# MCU.net
KiCad netlist of a schematic drawn in Altium Designer
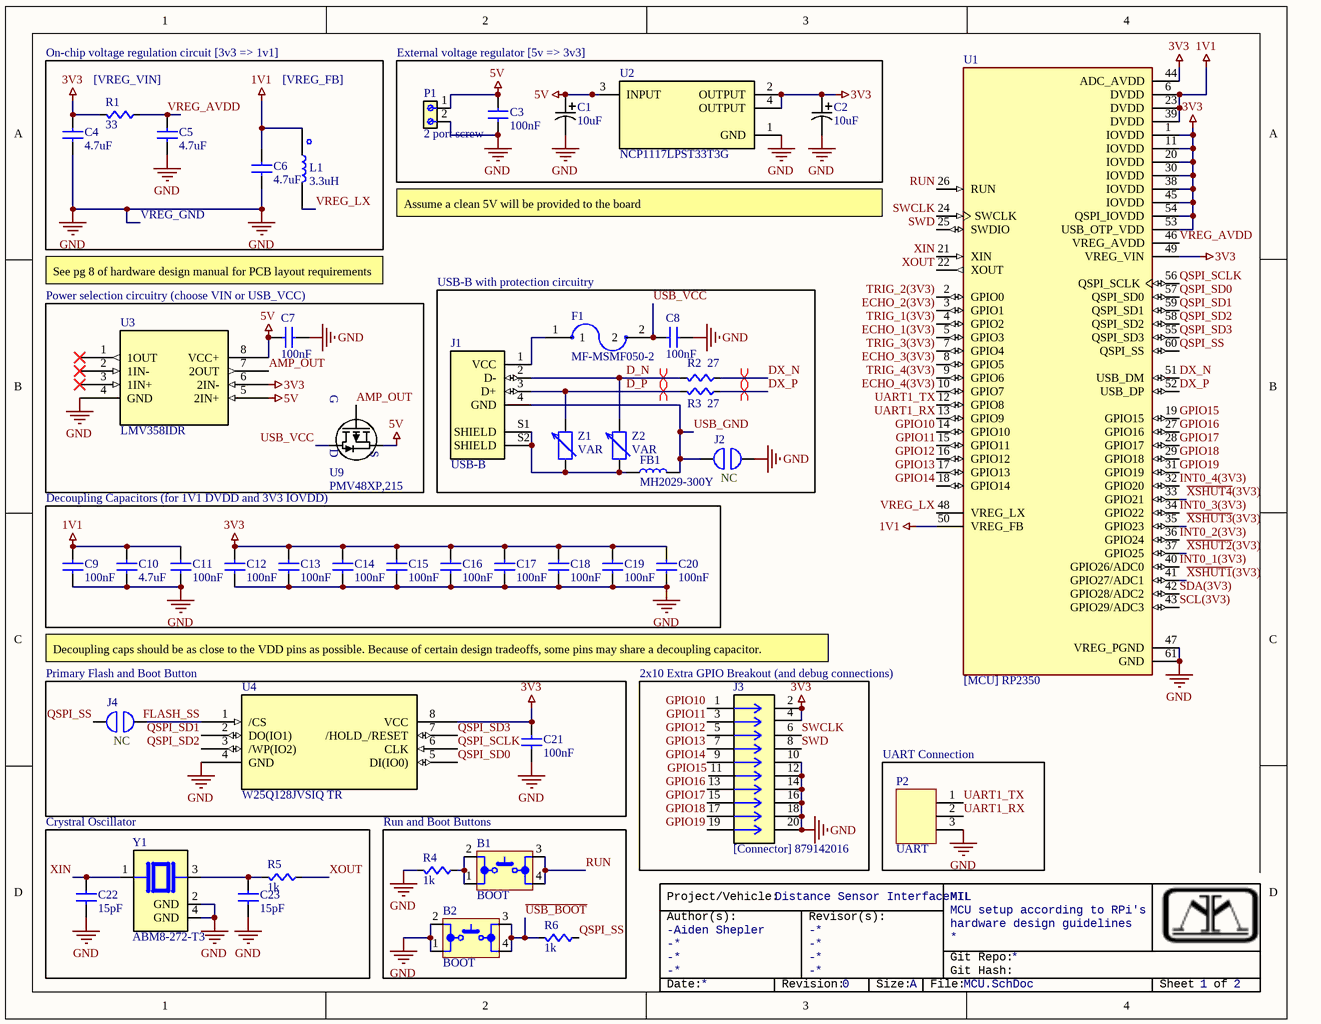
[diagram p0: MCU.SchDoc]

(export (version "E")
  (design (tool "Eeschema 10.0.6"))
  (components
    (comp (ref "B1")
      (value "BOOT")
      (footprint "SPST-PUSH-BUTTON")
      (description "SWITCH TACTILE SPST-NO 0.05A 24V")
      (fields
        (field (name "MANUFACTURER") "TE Connectivity Alcoswitch")
        (field (name "MANUFACTURER PART NUMBER") "1825910-6")
      )
      (libsource (lib "Alexandria") (part "1825910-6"))
    )
    (comp (ref "B2")
      (value "BOOT")
      (footprint "SPST-PUSH-BUTTON")
      (description "SWITCH TACTILE SPST-NO 0.05A 24V")
      (fields
        (field (name "MANUFACTURER") "TE Connectivity Alcoswitch")
        (field (name "MANUFACTURER PART NUMBER") "1825910-6")
      )
      (libsource (lib "Alexandria") (part "1825910-6"))
    )
    (comp (ref "C1")
      (value "10uF")
      (footprint "RADIAL_CAN_CAP_4_X_5.8_SMD")
      (description "10uF electrolytic cap, radial can, SMD")
      (fields
        (field (name "MANUFACTURER_PART_NUMBER") "EEE-FK1E100R")
        (field (name "COPYRIGHT") "Copyright (C) 2025 Ultra Librarian. All rights reserved.")
      )
      (libsource (lib "Alexandria") (part "EEE-FK1E100R"))
    )
    (comp (ref "C2")
      (value "10uF")
      (footprint "RADIAL_CAN_CAP_4_X_5.8_SMD")
      (description "10uF electrolytic cap, radial can, SMD")
      (fields
        (field (name "MANUFACTURER_PART_NUMBER") "EEE-FK1E100R")
        (field (name "COPYRIGHT") "Copyright (C) 2025 Ultra Librarian. All rights reserved.")
      )
      (libsource (lib "Alexandria") (part "EEE-FK1E100R"))
    )
    (comp (ref "C3")
      (value "100nF")
      (footprint "CAPC0603")
      (fields (field (name "Comment") "Cap"))
      (libsource (lib "Passives") (part "Cap"))
    )
    (comp (ref "C4")
      (value "4.7uF")
      (footprint "CAPC0603")
      (fields (field (name "Comment") "Cap"))
      (libsource (lib "Passives") (part "Cap"))
    )
    (comp (ref "C5")
      (value "4.7uF")
      (footprint "CAPC0603")
      (fields (field (name "Comment") "Cap"))
      (libsource (lib "Passives") (part "Cap"))
    )
    (comp (ref "C6")
      (value "4.7uF")
      (footprint "CAPC0603")
      (fields (field (name "Comment") "Cap"))
      (libsource (lib "Passives") (part "Cap"))
    )
    (comp (ref "C7")
      (value "100nF")
      (footprint "CAPC0603")
      (fields (field (name "Comment") "Cap"))
      (libsource (lib "Passives") (part "Cap"))
    )
    (comp (ref "C8")
      (value "100nF")
      (footprint "CAPC0603")
      (fields (field (name "Comment") "Cap"))
      (libsource (lib "Passives") (part "Cap"))
    )
    (comp (ref "C9")
      (value "100nF")
      (footprint "CAPC0603")
      (fields (field (name "Comment") "Cap"))
      (libsource (lib "Passives") (part "Cap"))
    )
    (comp (ref "C10")
      (value "4.7uF")
      (footprint "CAPC0603")
      (fields (field (name "Comment") "Cap"))
      (libsource (lib "Passives") (part "Cap"))
    )
    (comp (ref "C11")
      (value "100nF")
      (footprint "CAPC0603")
      (fields (field (name "Comment") "Cap"))
      (libsource (lib "Passives") (part "Cap"))
    )
    (comp (ref "C12")
      (value "100nF")
      (footprint "CAPC0603")
      (fields (field (name "Comment") "Cap"))
      (libsource (lib "Passives") (part "Cap"))
    )
    (comp (ref "C13")
      (value "100nF")
      (footprint "CAPC0603")
      (fields (field (name "Comment") "Cap"))
      (libsource (lib "Passives") (part "Cap"))
    )
    (comp (ref "C14")
      (value "100nF")
      (footprint "CAPC0603")
      (fields (field (name "Comment") "Cap"))
      (libsource (lib "Passives") (part "Cap"))
    )
    (comp (ref "C15")
      (value "100nF")
      (footprint "CAPC0603")
      (fields (field (name "Comment") "Cap"))
      (libsource (lib "Passives") (part "Cap"))
    )
    (comp (ref "C16")
      (value "100nF")
      (footprint "CAPC0603")
      (fields (field (name "Comment") "Cap"))
      (libsource (lib "Passives") (part "Cap"))
    )
    (comp (ref "C17")
      (value "100nF")
      (footprint "CAPC0603")
      (fields (field (name "Comment") "Cap"))
      (libsource (lib "Passives") (part "Cap"))
    )
    (comp (ref "C18")
      (value "100nF")
      (footprint "CAPC0603")
      (fields (field (name "Comment") "Cap"))
      (libsource (lib "Passives") (part "Cap"))
    )
    (comp (ref "C19")
      (value "100nF")
      (footprint "CAPC0603")
      (fields (field (name "Comment") "Cap"))
      (libsource (lib "Passives") (part "Cap"))
    )
    (comp (ref "C20")
      (value "100nF")
      (footprint "CAPC0603")
      (fields (field (name "Comment") "Cap"))
      (libsource (lib "Passives") (part "Cap"))
    )
    (comp (ref "C21")
      (value "100nF")
      (footprint "CAPC0603")
      (fields (field (name "Comment") "Cap"))
      (libsource (lib "Passives") (part "Cap"))
    )
    (comp (ref "C22")
      (value "15pF")
      (footprint "CAPC0603")
      (fields (field (name "Comment") "Cap"))
      (libsource (lib "Passives") (part "Cap"))
    )
    (comp (ref "C23")
      (value "15pF")
      (footprint "CAPC0603")
      (fields (field (name "Comment") "Cap"))
      (libsource (lib "Passives") (part "Cap"))
    )
    (comp (ref "F1")
      (value "MF-MSMF050-2")
      (footprint "FUSM4632X85")
      (description "[Fuse] Polymeric PTC Resettable Fuse 15V 500 mA Ih Surface Mount 1812 (4532 Metric), Concave")
      (fields (field (name "MF") "Bourns"))
      (libsource (lib "Alexandria") (part "MF-MSMF050-2"))
    )
    (comp (ref "FB1")
      (value "MH2029-300Y")
      (footprint "L0805")
      (description "[Inductor] Ferrite Bead Bourns MH2029-300Y\r\nSMD-FERRITE-BEAD-30R-3A(0805)")
      (fields (field (name "MF") "Bourns"))
      (libsource (lib "Alexandria") (part "MH2029-300Y"))
    )
    (comp (ref "J1")
      (value "USB-B")
      (footprint "SAMTEC_USB-B-S-X-X-TH")
      (description "USB-B (USB TYPE-B) USB 2.0 Receptacle Connector 4 Position Through Hole, Right Angle")
      (fields (field (name "MF") "Samtec") (field (name "MP") "USB-B-S-F-W-TH-TR"))
      (libsource (lib "Alexandria") (part "USB-B-S-X-X-TH"))
    )
    (comp (ref "J2")
      (value "Thru-Hole Jumper")
      (footprint "[Jumper] Solderable Jumper")
      (description "Clip Jumper")
      (fields (field (name "NO/NC") "NC"))
      (libsource (lib "Alexandria") (part "[Jump] Thru-Hole 2pin"))
    )
    (comp (ref "J3")
      (value "[Connector] 879142016")
      (footprint "[Connector] CONN20")
      (description "2x10 2.54mm pitch header")
      (fields (field (name "MP") "879142016"))
      (libsource (lib "Alexandria") (part "[Connector] 879142016"))
    )
    (comp (ref "J4")
      (value "Thru-Hole Jumper")
      (footprint "[Jumper] Solderable Jumper")
      (description "Clip Jumper")
      (fields (field (name "NO/NC") "NC"))
      (libsource (lib "Alexandria") (part "[Jump] Thru-Hole 2pin"))
    )
    (comp (ref "L1")
      (value "3.3uH")
      (footprint "2016_SMD_Inductor")
      (description "Power Inductors - SMD IND 3.3uH used for RP2350 VREG")
      (fields
        (field (name "MOUSER PART NUMBER") "815-AB201610S3R3101T")
        (field (name "MANUFACTURER_PART_NUMBER") "AOTA-B201610S3R3-101-T")
      )
      (libsource (lib "Alexandria") (part "INDUCTOR 3.3uH"))
    )
    (comp (ref "P1")
      (value "2 port screw")
      (footprint "[CONNECTOR] 5MM_2PORT_SCREW")
      (description "2 Position Wire to Board Terminal Block Horizontal with Board 0.200 (5.08mm) Through Hole")
      (fields (field (name "MF") "WÃ¼rth Elektronik") (field (name "MP") "691213510002"))
      (libsource (lib "Alexandria") (part "[Connector] 691213510002"))
    )
    (comp (ref "P2")
      (value "UART")
      (footprint "MOLEX-HDR-1X3-SHERLOCK-RA")
      (description "Header, Molex, 2mm Pitch Sherlock Header, Single Row, Right Angle 3 Circuits, Length 3.3mm")
      (fields
        (field (name "MANUFACTURER PART NUMBER") "35363-0360")
        (field (name "MANUFACTURER") "Molex Connector Corporation")
      )
      (libsource (lib "Connectors") (part "MOLEX-HDR-1x3-SHERLOCK_RA"))
    )
    (comp (ref "R1")
      (value "33")
      (footprint "RES0603")
      (description "SMD, RES0603")
      (fields (field (name "Comment") "Res"))
      (libsource (lib "Passives") (part "Res"))
    )
    (comp (ref "R2")
      (value "27")
      (footprint "RES0603")
      (description "SMD, RES0603")
      (fields (field (name "Comment") "Res"))
      (libsource (lib "Passives") (part "Res"))
    )
    (comp (ref "R3")
      (value "27")
      (footprint "RES0603")
      (description "SMD, RES0603")
      (fields (field (name "Comment") "Res"))
      (libsource (lib "Passives") (part "Res"))
    )
    (comp (ref "R4")
      (value "1k")
      (footprint "RES0603")
      (description "SMD, RES0603")
      (fields (field (name "Comment") "Res"))
      (libsource (lib "Passives") (part "Res"))
    )
    (comp (ref "R5")
      (value "1k")
      (footprint "RES0603")
      (description "SMD, RES0603")
      (fields (field (name "Comment") "Res"))
      (libsource (lib "Passives") (part "Res"))
    )
    (comp (ref "R6")
      (value "1k")
      (footprint "RES0603")
      (description "SMD, RES0603")
      (fields (field (name "Comment") "Res"))
      (libsource (lib "Passives") (part "Res"))
    )
    (comp (ref "U1")
      (value "[MCU] RP2350")
      (footprint "QFN40P700X700X90-61N")
      (description "RP2350A MCU from Raspberry Pi Pico; QFN 60 7x7,")
      (fields (field (name "MF") "Raspberry Pi") (field (name "MP") "SC1509-A4"))
      (libsource (lib "Alexandria") (part "SC1509(13)"))
    )
    (comp (ref "U2")
      (value "NCP1117LPST33T3G")
      (footprint "SOT230P700X175-4N")
      (description "Linear Voltage Regulator IC Positive Fixed 1 Output 1A SOT-223")
      (fields (field (name "MF") "ON Semiconductor"))
      (libsource (lib "Alexandria") (part "NCP1117LPST33T3G"))
    )
    (comp (ref "U3")
      (value "LMV358IDR")
      (footprint "SOIC-8")
      (description "[Op-Amp] Dual, 5.5-V, 1-MHz, RRO operational amplifier 8-SOIC -40 to 125")
      (fields (field (name "COPYRIGHT") "Copyright (C) 2025 Ultra Librarian. All rights reserved."))
      (libsource (lib "Alexandria") (part "LMV358IDR"))
    )
    (comp (ref "U4")
      (value "W25Q128JVSIQ TR")
      (footprint "SOIC_208MIL_WIN")
      (description "IC FLASH 128MBIT SPI/QUAD 8SOIC")
      (fields (field (name "COPYRIGHT") "Copyright (C) 2025 Ultra Librarian. All rights reserved."))
      (libsource (lib "Alexandria") (part "W25Q128JVSIQ TR"))
    )
    (comp (ref "U9")
      (value "PMV48XP,215")
      (footprint "SOT23_NEX")
      (description "MOSFET P-CH 20V 3.5A TO236AB")
      (fields (field (name "COPYRIGHT") "Copyright (C) 2025 Ultra Librarian. All rights reserved."))
      (libsource (lib "Alexandria") (part "[PMOS] PMV48XP,215"))
    )
    (comp (ref "Y1")
      (value "ABM8-272-T3")
      (footprint "XTAL_ABM8-272-T3")
      (description "12 MHz Â±30ppm Crystal 10pF 50 Ohms 4-SMD, No Lead")
      (fields (field (name "MF") "ABRACON"))
      (libsource (lib "Alexandria") (part "ABM8-272-T3"))
    )
    (comp (ref "Z1")
      (value "VAR")
      (footprint "VARC1608X56N")
      (description "[Varistor] 1 Circuit Surface Mount, MLCV 0603 (1608 Metric)")
      (fields (field (name "MP") "CG0603MLC-05E") (field (name "MF") "Bourns"))
      (libsource (lib "Alexandria") (part "CG0603MLC-05E"))
    )
    (comp (ref "Z2")
      (value "VAR")
      (footprint "VARC1608X56N")
      (description "[Varistor] 1 Circuit Surface Mount, MLCV 0603 (1608 Metric)")
      (fields (field (name "MP") "CG0603MLC-05E") (field (name "MF") "Bourns"))
      (libsource (lib "Alexandria") (part "CG0603MLC-05E"))
    )
  )
  (nets
    (net (code "1") (name "/AMP_OUT") (class "Default")
      (node (ref "U3") (pin "7") (pinfunction "2OUT_7") (pintype "output"))
      (node (ref "U9") (pin "1") (pinfunction "G_1") (pintype "passive"))
    )
    (net (code "2") (name "/DX_N") (class "Default")
      (node (ref "R2") (pin "2") (pinfunction "B_2") (pintype "passive"))
      (node (ref "U1") (pin "51") (pinfunction "USB_DM_51") (pintype "bidirectional"))
    )
    (net (code "3") (name "/DX_P") (class "Default")
      (node (ref "R3") (pin "2") (pinfunction "B_2") (pintype "passive"))
      (node (ref "U1") (pin "52") (pinfunction "USB_DP_52") (pintype "bidirectional"))
    )
    (net (code "4") (name "/D_N") (class "Default")
      (node (ref "J1") (pin "2") (pinfunction "D-_2") (pintype "bidirectional"))
      (node (ref "R2") (pin "1") (pinfunction "A_1") (pintype "passive"))
      (node (ref "Z2") (pin "2") (pinfunction "2_2") (pintype "passive"))
    )
    (net (code "5") (name "/D_P") (class "Default")
      (node (ref "J1") (pin "3") (pinfunction "D+_3") (pintype "bidirectional"))
      (node (ref "R3") (pin "1") (pinfunction "A_1") (pintype "passive"))
      (node (ref "Z1") (pin "2") (pinfunction "2_2") (pintype "passive"))
    )
    (net (code "6") (name "/ECHO_1(3V3)") (class "Default")
      (node (ref "U1") (pin "5") (pinfunction "GPIO3_5") (pintype "bidirectional"))
    )
    (net (code "7") (name "/ECHO_2(3V3)") (class "Default")
      (node (ref "U1") (pin "3") (pinfunction "GPIO1_3") (pintype "bidirectional"))
    )
    (net (code "8") (name "/ECHO_3(3V3)") (class "Default")
      (node (ref "U1") (pin "8") (pinfunction "GPIO5_8") (pintype "bidirectional"))
    )
    (net (code "9") (name "/ECHO_4(3V3)") (class "Default")
      (node (ref "U1") (pin "10") (pinfunction "GPIO7_10") (pintype "bidirectional"))
    )
    (net (code "10") (name "/FLASH_SS") (class "Default")
      (node (ref "J4") (pin "2") (pintype "passive"))
      (node (ref "U4") (pin "1") (pinfunction "/CS_1") (pintype "input"))
    )
    (net (code "11") (name "/GPIO10") (class "Default")
      (node (ref "J3") (pin "1") (pinfunction "1_1") (pintype "passive"))
      (node (ref "U1") (pin "14") (pinfunction "GPIO10_14") (pintype "bidirectional"))
    )
    (net (code "12") (name "/GPIO11") (class "Default")
      (node (ref "J3") (pin "3") (pinfunction "3_3") (pintype "passive"))
      (node (ref "U1") (pin "15") (pinfunction "GPIO11_15") (pintype "bidirectional"))
    )
    (net (code "13") (name "/GPIO12") (class "Default")
      (node (ref "J3") (pin "5") (pinfunction "5_5") (pintype "passive"))
      (node (ref "U1") (pin "16") (pinfunction "GPIO12_16") (pintype "bidirectional"))
    )
    (net (code "14") (name "/GPIO13") (class "Default")
      (node (ref "J3") (pin "7") (pinfunction "7_7") (pintype "passive"))
      (node (ref "U1") (pin "17") (pinfunction "GPIO13_17") (pintype "bidirectional"))
    )
    (net (code "15") (name "/GPIO14") (class "Default")
      (node (ref "J3") (pin "9") (pinfunction "9_9") (pintype "passive"))
      (node (ref "U1") (pin "18") (pinfunction "GPIO14_18") (pintype "bidirectional"))
    )
    (net (code "16") (name "/GPIO15") (class "Default")
      (node (ref "J3") (pin "11") (pinfunction "11_11") (pintype "passive"))
      (node (ref "U1") (pin "19") (pinfunction "GPIO15_19") (pintype "bidirectional"))
    )
    (net (code "17") (name "/GPIO16") (class "Default")
      (node (ref "J3") (pin "13") (pinfunction "13_13") (pintype "passive"))
      (node (ref "U1") (pin "27") (pinfunction "GPIO16_27") (pintype "bidirectional"))
    )
    (net (code "18") (name "/GPIO17") (class "Default")
      (node (ref "J3") (pin "15") (pinfunction "15_15") (pintype "passive"))
      (node (ref "U1") (pin "28") (pinfunction "GPIO17_28") (pintype "bidirectional"))
    )
    (net (code "19") (name "/GPIO18") (class "Default")
      (node (ref "J3") (pin "17") (pinfunction "17_17") (pintype "passive"))
      (node (ref "U1") (pin "29") (pinfunction "GPIO18_29") (pintype "bidirectional"))
    )
    (net (code "20") (name "/GPIO19") (class "Default")
      (node (ref "J3") (pin "19") (pinfunction "19_19") (pintype "passive"))
      (node (ref "U1") (pin "31") (pinfunction "GPIO19_31") (pintype "bidirectional"))
    )
    (net (code "21") (name "/INT0_1(3V3)") (class "Default")
      (node (ref "U1") (pin "40") (pinfunction "GPIO26/ADC0_40") (pintype "bidirectional"))
    )
    (net (code "22") (name "/INT0_2(3V3)") (class "Default")
      (node (ref "U1") (pin "36") (pinfunction "GPIO24_36") (pintype "bidirectional"))
    )
    (net (code "23") (name "/INT0_3(3V3)") (class "Default")
      (node (ref "U1") (pin "34") (pinfunction "GPIO22_34") (pintype "bidirectional"))
    )
    (net (code "24") (name "/INT0_4(3V3)") (class "Default")
      (node (ref "U1") (pin "32") (pinfunction "GPIO20_32") (pintype "bidirectional"))
    )
    (net (code "25") (name "/QSPI_SCLK") (class "Default")
      (node (ref "U1") (pin "56") (pinfunction "QSPI_SCLK_56") (pintype "bidirectional"))
      (node (ref "U4") (pin "6") (pinfunction "CLK_6") (pintype "input"))
    )
    (net (code "26") (name "/QSPI_SD0") (class "Default")
      (node (ref "U1") (pin "57") (pinfunction "QSPI_SD0_57") (pintype "bidirectional"))
      (node (ref "U4") (pin "5") (pinfunction "DI(IO0)_5") (pintype "bidirectional"))
    )
    (net (code "27") (name "/QSPI_SD1") (class "Default")
      (node (ref "U1") (pin "59") (pinfunction "QSPI_SD1_59") (pintype "bidirectional"))
      (node (ref "U4") (pin "2") (pinfunction "DO(IO1)_2") (pintype "bidirectional"))
    )
    (net (code "28") (name "/QSPI_SD2") (class "Default")
      (node (ref "U1") (pin "58") (pinfunction "QSPI_SD2_58") (pintype "bidirectional"))
      (node (ref "U4") (pin "3") (pinfunction "/WP(IO2)_3") (pintype "bidirectional"))
    )
    (net (code "29") (name "/QSPI_SD3") (class "Default")
      (node (ref "U1") (pin "55") (pinfunction "QSPI_SD3_55") (pintype "bidirectional"))
      (node (ref "U4") (pin "7") (pinfunction "/HOLD_/RESET_7") (pintype "bidirectional"))
    )
    (net (code "30") (name "/QSPI_SS") (class "Default")
      (node (ref "J4") (pin "1") (pintype "passive"))
      (node (ref "R6") (pin "2") (pinfunction "B_2") (pintype "passive"))
      (node (ref "U1") (pin "60") (pinfunction "QSPI_SS_60") (pintype "bidirectional"))
    )
    (net (code "31") (name "/RUN") (class "Default")
      (node (ref "B1") (pin "3") (pinfunction "3_3") (pintype "passive"))
      (node (ref "B1") (pin "4") (pinfunction "4_4") (pintype "passive"))
      (node (ref "U1") (pin "26") (pinfunction "RUN_26") (pintype "input"))
    )
    (net (code "32") (name "/SCL(3V3)") (class "Default")
      (node (ref "U1") (pin "43") (pinfunction "GPIO29/ADC3_43") (pintype "bidirectional"))
    )
    (net (code "33") (name "/SDA(3V3)") (class "Default")
      (node (ref "U1") (pin "42") (pinfunction "GPIO28/ADC2_42") (pintype "bidirectional"))
    )
    (net (code "34") (name "/SWCLK") (class "Default")
      (node (ref "J3") (pin "6") (pinfunction "6_6") (pintype "passive"))
      (node (ref "U1") (pin "24") (pinfunction "SWCLK_24") (pintype "input"))
    )
    (net (code "35") (name "/SWD") (class "Default")
      (node (ref "J3") (pin "8") (pinfunction "8_8") (pintype "passive"))
      (node (ref "U1") (pin "25") (pinfunction "SWDIO_25") (pintype "bidirectional"))
    )
    (net (code "36") (name "/TRIG_1(3V3)") (class "Default")
      (node (ref "U1") (pin "4") (pinfunction "GPIO2_4") (pintype "bidirectional"))
    )
    (net (code "37") (name "/TRIG_2(3V3)") (class "Default")
      (node (ref "U1") (pin "2") (pinfunction "GPIO0_2") (pintype "bidirectional"))
    )
    (net (code "38") (name "/TRIG_3(3V3)") (class "Default")
      (node (ref "U1") (pin "7") (pinfunction "GPIO4_7") (pintype "bidirectional"))
    )
    (net (code "39") (name "/TRIG_4(3V3)") (class "Default")
      (node (ref "U1") (pin "9") (pinfunction "GPIO6_9") (pintype "bidirectional"))
    )
    (net (code "40") (name "/UART1_RX") (class "Default")
      (node (ref "P2") (pin "2") (pinfunction "2_2") (pintype "passive"))
      (node (ref "U1") (pin "13") (pinfunction "GPIO9_13") (pintype "bidirectional"))
    )
    (net (code "41") (name "/UART1_TX") (class "Default")
      (node (ref "P2") (pin "1") (pinfunction "1_1") (pintype "passive"))
      (node (ref "U1") (pin "12") (pinfunction "GPIO8_12") (pintype "bidirectional"))
    )
    (net (code "42") (name "/USB_GND") (class "Default")
      (node (ref "FB1") (pin "2") (pinfunction "2_2") (pintype "passive"))
      (node (ref "J1") (pin "4") (pinfunction "GND_4") (pintype "power_in"))
      (node (ref "J2") (pin "1") (pintype "passive"))
    )
    (net (code "43") (name "/USB_VCC") (class "Default")
      (node (ref "C8") (pin "2") (pinfunction "B_2") (pintype "passive"))
      (node (ref "F1") (pin "2") (pinfunction "2_2") (pintype "passive"))
      (node (ref "U9") (pin "3") (pinfunction "D_3") (pintype "passive"))
    )
    (net (code "44") (name "/VREG_AVDD") (class "Default")
      (node (ref "C5") (pin "1") (pinfunction "A_1") (pintype "passive"))
      (node (ref "R1") (pin "2") (pinfunction "B_2") (pintype "passive"))
      (node (ref "U1") (pin "46") (pinfunction "VREG_AVDD_46") (pintype "power_in"))
    )
    (net (code "45") (name "/VREG_LX") (class "Default")
      (node (ref "L1") (pin "2") (pinfunction "2_2") (pintype "passive"))
      (node (ref "U1") (pin "48") (pinfunction "VREG_LX_48") (pintype "passive"))
    )
    (net (code "46") (name "/XIN") (class "Default")
      (node (ref "C22") (pin "1") (pinfunction "A_1") (pintype "passive"))
      (node (ref "U1") (pin "21") (pinfunction "XIN_21") (pintype "input"))
      (node (ref "Y1") (pin "1") (pinfunction "1_1") (pintype "passive"))
    )
    (net (code "47") (name "/XOUT") (class "Default")
      (node (ref "R5") (pin "2") (pinfunction "B_2") (pintype "passive"))
      (node (ref "U1") (pin "22") (pinfunction "XOUT_22") (pintype "output"))
    )
    (net (code "48") (name "/~{USB_BOOT}") (class "Default")
      (node (ref "B2") (pin "3") (pinfunction "3_3") (pintype "passive"))
      (node (ref "B2") (pin "4") (pinfunction "4_4") (pintype "passive"))
      (node (ref "R6") (pin "1") (pinfunction "A_1") (pintype "passive"))
    )
    (net (code "49") (name "/~{XSHUT1}(3V3)") (class "Default")
      (node (ref "U1") (pin "41") (pinfunction "GPIO27/ADC1_41") (pintype "bidirectional"))
    )
    (net (code "50") (name "/~{XSHUT2}(3V3)") (class "Default")
      (node (ref "U1") (pin "37") (pinfunction "GPIO25_37") (pintype "bidirectional"))
    )
    (net (code "51") (name "/~{XSHUT3}(3V3)") (class "Default")
      (node (ref "U1") (pin "35") (pinfunction "GPIO23_35") (pintype "bidirectional"))
    )
    (net (code "52") (name "/~{XSHUT4}(3V3)") (class "Default")
      (node (ref "U1") (pin "33") (pinfunction "GPIO21_33") (pintype "bidirectional"))
    )
    (net (code "53") (name "1V1") (class "Default")
      (node (ref "C10") (pin "1") (pinfunction "A_1") (pintype "passive"))
      (node (ref "C11") (pin "1") (pinfunction "A_1") (pintype "passive"))
      (node (ref "C6") (pin "1") (pinfunction "A_1") (pintype "passive"))
      (node (ref "C9") (pin "1") (pinfunction "A_1") (pintype "passive"))
      (node (ref "L1") (pin "1") (pinfunction "1_1") (pintype "passive"))
      (node (ref "U1") (pin "23") (pinfunction "DVDD_23") (pintype "power_in"))
      (node (ref "U1") (pin "39") (pinfunction "DVDD_39") (pintype "power_in"))
      (node (ref "U1") (pin "50") (pinfunction "VREG_FB_50") (pintype "passive"))
      (node (ref "U1") (pin "6") (pinfunction "DVDD_6") (pintype "power_in"))
    )
    (net (code "54") (name "3V3") (class "Default")
      (node (ref "C12") (pin "1") (pinfunction "A_1") (pintype "passive"))
      (node (ref "C13") (pin "1") (pinfunction "A_1") (pintype "passive"))
      (node (ref "C14") (pin "1") (pinfunction "A_1") (pintype "passive"))
      (node (ref "C15") (pin "1") (pinfunction "A_1") (pintype "passive"))
      (node (ref "C16") (pin "1") (pinfunction "A_1") (pintype "passive"))
      (node (ref "C17") (pin "1") (pinfunction "A_1") (pintype "passive"))
      (node (ref "C18") (pin "1") (pinfunction "A_1") (pintype "passive"))
      (node (ref "C19") (pin "1") (pinfunction "A_1") (pintype "passive"))
      (node (ref "C2") (pin "1") (pinfunction "1_1") (pintype "passive"))
      (node (ref "C20") (pin "1") (pinfunction "A_1") (pintype "passive"))
      (node (ref "C21") (pin "1") (pinfunction "A_1") (pintype "passive"))
      (node (ref "C4") (pin "1") (pinfunction "A_1") (pintype "passive"))
      (node (ref "J3") (pin "2") (pinfunction "2_2") (pintype "passive"))
      (node (ref "J3") (pin "4") (pinfunction "4_4") (pintype "passive"))
      (node (ref "R1") (pin "1") (pinfunction "A_1") (pintype "passive"))
      (node (ref "U1") (pin "1") (pinfunction "IOVDD_1") (pintype "power_in"))
      (node (ref "U1") (pin "11") (pinfunction "IOVDD_11") (pintype "power_in"))
      (node (ref "U1") (pin "20") (pinfunction "IOVDD_20") (pintype "power_in"))
      (node (ref "U1") (pin "30") (pinfunction "IOVDD_30") (pintype "power_in"))
      (node (ref "U1") (pin "38") (pinfunction "IOVDD_38") (pintype "power_in"))
      (node (ref "U1") (pin "44") (pinfunction "ADC_AVDD_44") (pintype "power_in"))
      (node (ref "U1") (pin "45") (pinfunction "IOVDD_45") (pintype "power_in"))
      (node (ref "U1") (pin "49") (pinfunction "VREG_VIN_49") (pintype "power_in"))
      (node (ref "U1") (pin "53") (pinfunction "USB_OTP_VDD_53") (pintype "power_in"))
      (node (ref "U1") (pin "54") (pinfunction "QSPI_IOVDD_54") (pintype "power_in"))
      (node (ref "U2") (pin "2") (pinfunction "OUTPUT_2") (pintype "passive"))
      (node (ref "U2") (pin "4") (pinfunction "OUTPUT_4") (pintype "passive"))
      (node (ref "U3") (pin "6") (pinfunction "2IN-_6") (pintype "input"))
      (node (ref "U4") (pin "8") (pinfunction "VCC_8") (pintype "power_in"))
    )
    (net (code "55") (name "5V") (class "Default")
      (node (ref "C1") (pin "1") (pinfunction "1_1") (pintype "passive"))
      (node (ref "C3") (pin "1") (pinfunction "A_1") (pintype "passive"))
      (node (ref "C7") (pin "1") (pinfunction "A_1") (pintype "passive"))
      (node (ref "P1") (pin "1") (pinfunction "1_1") (pintype "passive"))
      (node (ref "U2") (pin "3") (pinfunction "INPUT_3") (pintype "passive"))
      (node (ref "U3") (pin "5") (pinfunction "2IN+_5") (pintype "input"))
      (node (ref "U3") (pin "8") (pinfunction "VCC+_8") (pintype "power_in"))
      (node (ref "U9") (pin "2") (pinfunction "S_2") (pintype "passive"))
    )
    (net (code "56") (name "GND") (class "Default")
      (node (ref "B2") (pin "1") (pinfunction "1_1") (pintype "passive"))
      (node (ref "B2") (pin "2") (pinfunction "2_2") (pintype "passive"))
      (node (ref "C1") (pin "2") (pinfunction "2_2") (pintype "passive"))
      (node (ref "C10") (pin "2") (pinfunction "B_2") (pintype "passive"))
      (node (ref "C11") (pin "2") (pinfunction "B_2") (pintype "passive"))
      (node (ref "C12") (pin "2") (pinfunction "B_2") (pintype "passive"))
      (node (ref "C13") (pin "2") (pinfunction "B_2") (pintype "passive"))
      (node (ref "C14") (pin "2") (pinfunction "B_2") (pintype "passive"))
      (node (ref "C15") (pin "2") (pinfunction "B_2") (pintype "passive"))
      (node (ref "C16") (pin "2") (pinfunction "B_2") (pintype "passive"))
      (node (ref "C17") (pin "2") (pinfunction "B_2") (pintype "passive"))
      (node (ref "C18") (pin "2") (pinfunction "B_2") (pintype "passive"))
      (node (ref "C19") (pin "2") (pinfunction "B_2") (pintype "passive"))
      (node (ref "C2") (pin "2") (pinfunction "2_2") (pintype "passive"))
      (node (ref "C20") (pin "2") (pinfunction "B_2") (pintype "passive"))
      (node (ref "C21") (pin "2") (pinfunction "B_2") (pintype "passive"))
      (node (ref "C22") (pin "2") (pinfunction "B_2") (pintype "passive"))
      (node (ref "C23") (pin "2") (pinfunction "B_2") (pintype "passive"))
      (node (ref "C3") (pin "2") (pinfunction "B_2") (pintype "passive"))
      (node (ref "C4") (pin "2") (pinfunction "B_2") (pintype "passive"))
      (node (ref "C5") (pin "2") (pinfunction "B_2") (pintype "passive"))
      (node (ref "C6") (pin "2") (pinfunction "B_2") (pintype "passive"))
      (node (ref "C7") (pin "2") (pinfunction "B_2") (pintype "passive"))
      (node (ref "C8") (pin "1") (pinfunction "A_1") (pintype "passive"))
      (node (ref "C9") (pin "2") (pinfunction "B_2") (pintype "passive"))
      (node (ref "J2") (pin "2") (pintype "passive"))
      (node (ref "J3") (pin "10") (pinfunction "10_10") (pintype "passive"))
      (node (ref "J3") (pin "12") (pinfunction "12_12") (pintype "passive"))
      (node (ref "J3") (pin "14") (pinfunction "14_14") (pintype "passive"))
      (node (ref "J3") (pin "16") (pinfunction "16_16") (pintype "passive"))
      (node (ref "J3") (pin "18") (pinfunction "18_18") (pintype "passive"))
      (node (ref "J3") (pin "20") (pinfunction "20_20") (pintype "passive"))
      (node (ref "P1") (pin "2") (pinfunction "2_2") (pintype "passive"))
      (node (ref "P2") (pin "3") (pinfunction "3_3") (pintype "passive"))
      (node (ref "R4") (pin "1") (pinfunction "A_1") (pintype "passive"))
      (node (ref "U1") (pin "47") (pinfunction "VREG_PGND_47") (pintype "power_in"))
      (node (ref "U1") (pin "61") (pinfunction "GND_61") (pintype "power_in"))
      (node (ref "U2") (pin "1") (pinfunction "GND_1") (pintype "power_in"))
      (node (ref "U3") (pin "4") (pinfunction "GND_4") (pintype "power_in"))
      (node (ref "U4") (pin "4") (pinfunction "GND_4") (pintype "power_in"))
      (node (ref "Y1") (pin "2") (pinfunction "GND_2") (pintype "power_in"))
      (node (ref "Y1") (pin "4") (pinfunction "GND_4") (pintype "power_in"))
    )
    (net (code "57") (name "Net-(C23-A)") (class "Default")
      (node (ref "C23") (pin "1") (pinfunction "A_1") (pintype "passive"))
      (node (ref "R5") (pin "1") (pinfunction "A_1") (pintype "passive"))
      (node (ref "Y1") (pin "3") (pinfunction "3_3") (pintype "passive"))
    )
    (net (code "58") (name "Net-(FB1-Pad1)") (class "Default")
      (node (ref "FB1") (pin "1") (pinfunction "1_1") (pintype "passive"))
      (node (ref "J1") (pin "S1") (pinfunction "SHIELD_S1") (pintype "passive"))
      (node (ref "J1") (pin "S2") (pinfunction "SHIELD_S2") (pintype "passive"))
      (node (ref "Z1") (pin "1") (pinfunction "1_1") (pintype "passive"))
      (node (ref "Z2") (pin "1") (pinfunction "1_1") (pintype "passive"))
    )
    (net (code "59") (name "Net-(J1-VCC)") (class "Default")
      (node (ref "F1") (pin "1") (pinfunction "1_1") (pintype "passive"))
      (node (ref "J1") (pin "1") (pinfunction "VCC_1") (pintype "power_in"))
    )
    (net (code "60") (name "Net-(R4-B)") (class "Default")
      (node (ref "B1") (pin "1") (pinfunction "1_1") (pintype "passive"))
      (node (ref "B1") (pin "2") (pinfunction "2_2") (pintype "passive"))
      (node (ref "R4") (pin "2") (pinfunction "B_2") (pintype "passive"))
    )
    (net (code "61") (name "unconnected-(U3-1IN+-Pad3)") (class "Default")
      (node (ref "U3") (pin "3") (pinfunction "1IN+_3") (pintype "input+no_connect"))
    )
    (net (code "62") (name "unconnected-(U3-1IN--Pad2)") (class "Default")
      (node (ref "U3") (pin "2") (pinfunction "1IN-_2") (pintype "input+no_connect"))
    )
    (net (code "63") (name "unconnected-(U3-1OUT-Pad1)") (class "Default")
      (node (ref "U3") (pin "1") (pinfunction "1OUT_1") (pintype "output+no_connect"))
    )
  )
)
